# MCU.net
KiCad netlist of a schematic drawn in Altium Designer
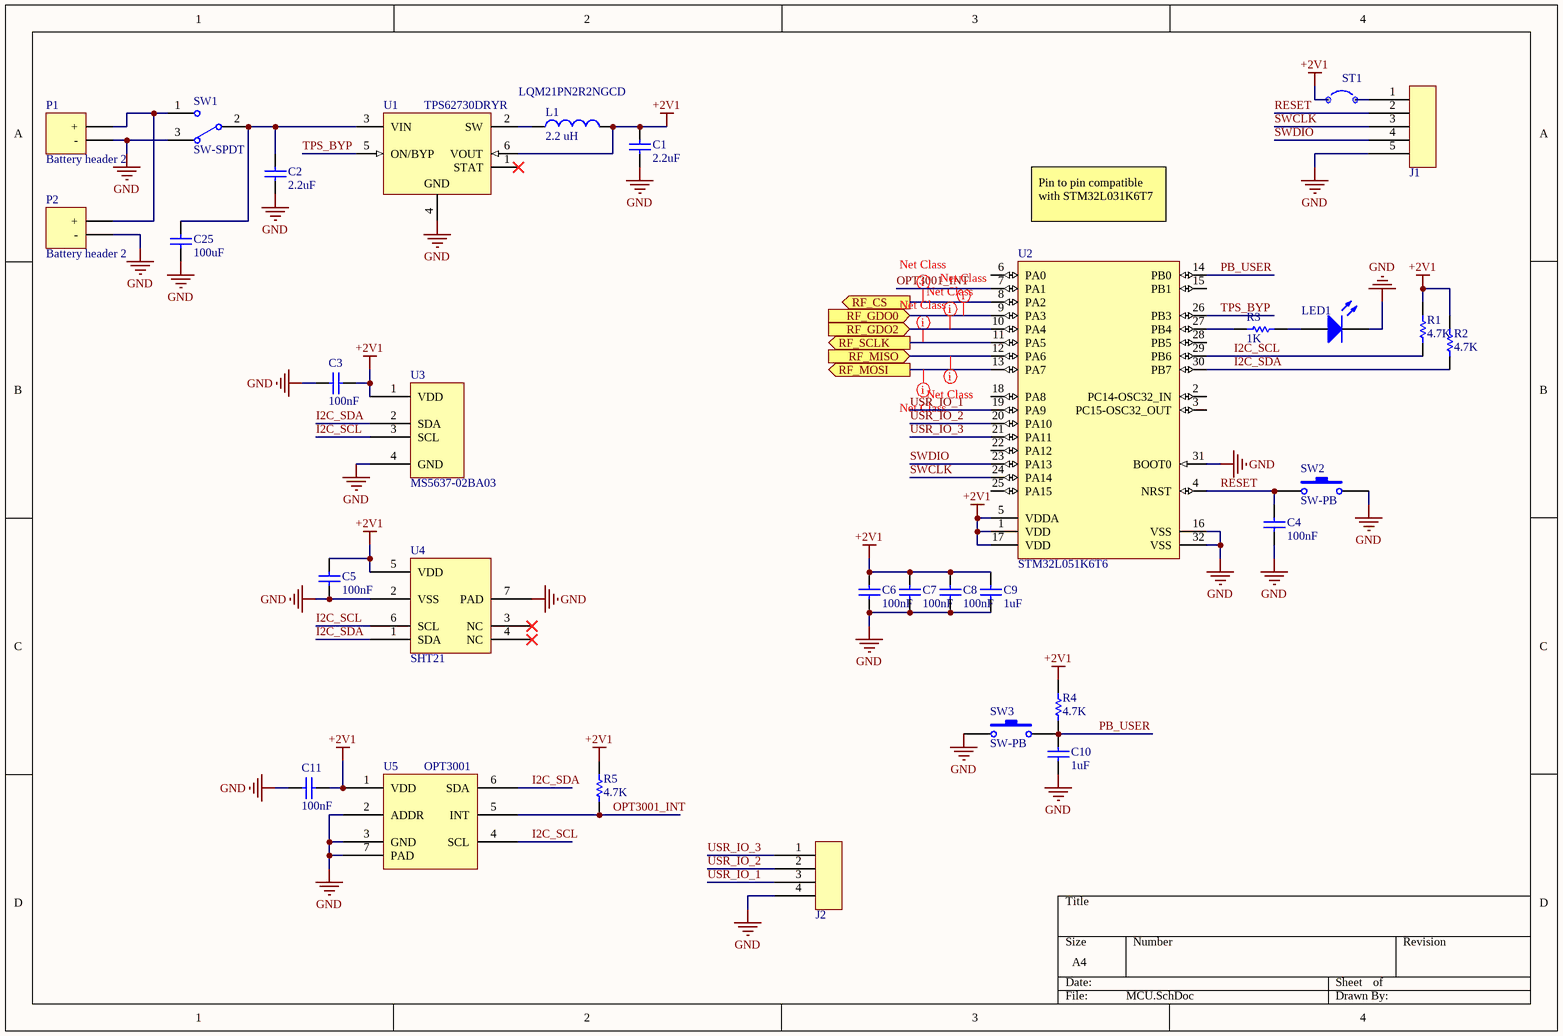
[diagram p0: MCU.SchDoc]

(export (version "E")
  (design (tool "Eeschema 10.0.6"))
  (components
    (comp (ref "C1")
      (value "2.2uF")
      (footprint "0402_ipc")
      (description "Capacitor")
      (fields
        (field (name "PARTNUMBER") "GRM155R60J225ME95D")
        (field (name "Comment") "Cap")
        (field (name "PUBLISHER") "Altium Limited")
      )
      (libsource (lib "LucasLib") (part "Cap"))
    )
    (comp (ref "C2")
      (value "2.2uF")
      (footprint "0402_ipc")
      (description "Capacitor")
      (fields
        (field (name "PARTNUMBER") "GRM155R60J225ME95D")
        (field (name "Comment") "Cap")
        (field (name "PUBLISHER") "Altium Limited")
      )
      (libsource (lib "LucasLib") (part "Cap"))
    )
    (comp (ref "C3")
      (value "100nF")
      (footprint "0402_ipc")
      (description "Capacitor")
      (fields
        (field (name "PARTNUMBER") "GRM155R71C104KA88D")
        (field (name "Comment") "Cap")
        (field (name "PUBLISHER") "Altium Limited")
      )
      (libsource (lib "LucasLib") (part "Cap"))
    )
    (comp (ref "C4")
      (value "100nF")
      (footprint "0402_ipc")
      (description "Capacitor")
      (fields
        (field (name "PARTNUMBER") "GRM155R71C104KA88D")
        (field (name "Comment") "Cap")
        (field (name "PUBLISHER") "Altium Limited")
      )
      (libsource (lib "LucasLib") (part "Cap"))
    )
    (comp (ref "C5")
      (value "100nF")
      (footprint "0402_ipc")
      (description "Capacitor")
      (fields
        (field (name "PARTNUMBER") "GRM155R71C104KA88D")
        (field (name "Comment") "Cap")
        (field (name "PUBLISHER") "Altium Limited")
      )
      (libsource (lib "LucasLib") (part "Cap"))
    )
    (comp (ref "C6")
      (value "100nF")
      (footprint "0402_ipc")
      (description "Capacitor")
      (fields
        (field (name "PARTNUMBER") "GRM155R71C104KA88D")
        (field (name "Comment") "Cap")
        (field (name "PUBLISHER") "Altium Limited")
      )
      (libsource (lib "LucasLib") (part "Cap"))
    )
    (comp (ref "C7")
      (value "100nF")
      (footprint "0402_ipc")
      (description "Capacitor")
      (fields
        (field (name "PARTNUMBER") "GRM155R71C104KA88D")
        (field (name "Comment") "Cap")
        (field (name "PUBLISHER") "Altium Limited")
      )
      (libsource (lib "LucasLib") (part "Cap"))
    )
    (comp (ref "C8")
      (value "100nF")
      (footprint "0402_ipc")
      (description "Capacitor")
      (fields
        (field (name "PARTNUMBER") "GRM155R71C104KA88D")
        (field (name "Comment") "Cap")
        (field (name "PUBLISHER") "Altium Limited")
      )
      (libsource (lib "LucasLib") (part "Cap"))
    )
    (comp (ref "C9")
      (value "1uF")
      (footprint "0402_ipc")
      (description "Capacitor")
      (fields
        (field (name "PARTNUMBER") "GRM155R61C105KA12D")
        (field (name "Comment") "Cap")
        (field (name "PUBLISHER") "Altium Limited")
      )
      (libsource (lib "LucasLib") (part "Cap"))
    )
    (comp (ref "C10")
      (value "1uF")
      (footprint "0402_ipc")
      (description "Capacitor")
      (fields
        (field (name "PARTNUMBER") "GRM155R61C105KA12D")
        (field (name "Comment") "Cap")
        (field (name "PUBLISHER") "Altium Limited")
      )
      (libsource (lib "LucasLib") (part "Cap"))
    )
    (comp (ref "C11")
      (value "100nF")
      (footprint "0402_ipc")
      (description "Capacitor")
      (fields
        (field (name "PARTNUMBER") "GRM155R71C104KA88D")
        (field (name "Comment") "Cap")
        (field (name "PUBLISHER") "Altium Limited")
      )
      (libsource (lib "LucasLib") (part "Cap"))
    )
    (comp (ref "C25")
      (value "100uF")
      (footprint "1206_IPC")
      (description "Capacitor")
      (fields
        (field (name "PARTNUMBER") "GRM31CR60J157ME11L")
        (field (name "Comment") "Cap")
        (field (name "PUBLISHER") "Altium Limited")
      )
      (libsource (lib "LucasLib") (part "Cap"))
    )
    (comp (ref "J1")
      (value "CONN_5")
      (footprint "MOLEX_5_1.27")
      (description "5 pin connector")
      (fields (field (name "PARTNUMBER") "53048-0510"))
      (libsource (lib "LucasLib") (part "CONN_5"))
    )
    (comp (ref "J2")
      (value "CONN_4")
      (footprint "HDR1X4_100mil")
      (description "4 pin connector")
      (fields (field (name "PARTNUMBER") "Pin Header"))
      (libsource (lib "LucasLib") (part "CONN_4"))
    )
    (comp (ref "L1")
      (value "2.2 uH")
      (footprint "0805_IPC")
      (description "Inductor")
      (fields (field (name "PARTNUMBER") "LQM21PN2R2NGCD"))
      (libsource (lib "LucasLib") (part "Inductor"))
    )
    (comp (ref "LED1")
      (value "LED")
      (footprint "0805_IPC")
      (fields (field (name "PARTNUMBER") "SML-H12M8TT86"))
      (libsource (lib "LucasLib") (part "LED"))
    )
    (comp (ref "P1")
      (value "Battery header 2")
      (footprint "HDR1X2_100mil")
      (fields (field (name "PARTNUMBER") "Pin Header") (field (name "PUBLISHER") "Altium Limited"))
      (libsource (lib "LucasLib") (part "Battery header 2"))
    )
    (comp (ref "P2")
      (value "Battery header 2")
      (footprint "SMTU2450N-LF")
      (fields (field (name "PARTNUMBER") "SMTU 2450N-1-LF") (field (name "PUBLISHER") "Altium Limited"))
      (libsource (lib "LucasLib") (part "Battery header 2"))
    )
    (comp (ref "R1")
      (value "4.7K")
      (footprint "0402_ipc")
      (description "Resistor")
      (fields (field (name "PARTNUMBER") "ERJ2GEJ472X") (field (name "Comment") "Res"))
      (libsource (lib "LucasLib") (part "Res"))
    )
    (comp (ref "R2")
      (value "4.7K")
      (footprint "0402_ipc")
      (description "Resistor")
      (fields (field (name "PARTNUMBER") "ERJ2GEJ472X") (field (name "Comment") "Res"))
      (libsource (lib "LucasLib") (part "Res"))
    )
    (comp (ref "R3")
      (value "1K")
      (footprint "0402_ipc")
      (description "Resistor")
      (fields (field (name "PARTNUMBER") "MC00625W040211K") (field (name "Comment") "Res"))
      (libsource (lib "LucasLib") (part "Res"))
    )
    (comp (ref "R4")
      (value "4.7K")
      (footprint "0402_ipc")
      (description "Resistor")
      (fields (field (name "PARTNUMBER") "ERJ2GEJ472X") (field (name "Comment") "Res"))
      (libsource (lib "LucasLib") (part "Res"))
    )
    (comp (ref "R5")
      (value "4.7K")
      (footprint "0402_ipc")
      (description "Resistor")
      (fields (field (name "PARTNUMBER") "ERJ2GEJ472X") (field (name "Comment") "Res"))
      (libsource (lib "LucasLib") (part "Res"))
    )
    (comp (ref "ST1") (value "STRAP") (footprint "STRAP") (libsource (lib "LucasLib") (part "STRAP")))
    (comp (ref "SW1")
      (value "SW-SPDT")
      (footprint "PCM12SMTR")
      (description "SPDT Switch")
      (fields (field (name "PARTNUMBER") "PCM12SMTR"))
      (libsource (lib "LucasLib") (part "SW-SPDT"))
    )
    (comp (ref "SW2")
      (value "SW-PB")
      (footprint "B3U-1000P")
      (description "Tactile Switch")
      (fields (field (name "PARTNUMBER") "B3U-1000P"))
      (libsource (lib "LucasLib") (part "SW-PB"))
    )
    (comp (ref "SW3")
      (value "SW-PB")
      (footprint "MCDTS-2")
      (description "Tactile Switch")
      (fields (field (name "PARTNUMBER") "MCDTS2-4N"))
      (libsource (lib "LucasLib") (part "SW-PB"))
    )
    (comp (ref "U1")
      (value "TPS62730DRYR")
      (footprint "DRY6")
      (fields (field (name "MANUFACTURER") "Texas Instruments") (field (name "PARTNUMBER") "TPS62730DRYT"))
      (libsource (lib "TI Power Management Step-Down Regulator") (part "TPS62730DRYR"))
    )
    (comp (ref "U2")
      (value "STM32L051K6T6")
      (footprint "STM-LQFP32_L")
      (fields (field (name "PARTNUMBER") "STM32L031K6T7") (field (name "MANUFACTURER") "STMicroelectronics"))
      (libsource (lib "Altium Content Vault") (part "CMP-1341-00001-1"))
    )
    (comp (ref "U3")
      (value "MS5637-02BA03")
      (footprint "MS5637-02BA03")
      (description "Low Voltage Barometric Pressure Sensor")
      (fields (field (name "PARTNUMBER") "MS563702BA03-50"))
      (libsource (lib "LucasLib") (part "MS5637-02BA03"))
    )
    (comp (ref "U4")
      (value "SHT21")
      (footprint "SHT21")
      (description "Humidity and Temperature Sensor")
      (libsource (lib "LucasLib") (part "SHT21"))
    )
    (comp (ref "U5")
      (value "OPT3001")
      (footprint "OPT3001")
      (description "Light sensor")
      (fields (field (name "PARTNUMBER") "OPT3001DNPT"))
      (libsource (lib "LucasLib") (part "OPT3001"))
    )
  )
  (nets
    (net (code "1") (name "+2V1") (class "Default")
      (node (ref "C1") (pin "2") (pinfunction "2_2") (pintype "passive"))
      (node (ref "C11") (pin "2") (pinfunction "2_2") (pintype "passive"))
      (node (ref "C3") (pin "1") (pinfunction "1_1") (pintype "passive"))
      (node (ref "C5") (pin "1") (pinfunction "1_1") (pintype "passive"))
      (node (ref "C6") (pin "2") (pinfunction "2_2") (pintype "passive"))
      (node (ref "C7") (pin "2") (pinfunction "2_2") (pintype "passive"))
      (node (ref "C8") (pin "2") (pinfunction "2_2") (pintype "passive"))
      (node (ref "C9") (pin "2") (pinfunction "2_2") (pintype "passive"))
      (node (ref "L1") (pin "2") (pinfunction "2_2") (pintype "passive"))
      (node (ref "R1") (pin "2") (pinfunction "2_2") (pintype "passive"))
      (node (ref "R2") (pin "2") (pinfunction "2_2") (pintype "passive"))
      (node (ref "R4") (pin "2") (pinfunction "2_2") (pintype "passive"))
      (node (ref "R5") (pin "2") (pinfunction "2_2") (pintype "passive"))
      (node (ref "ST1") (pin "1") (pintype "passive"))
      (node (ref "U1") (pin "6") (pinfunction "VOUT_6") (pintype "input"))
      (node (ref "U2") (pin "1") (pinfunction "VDD_1") (pintype "power_in"))
      (node (ref "U2") (pin "17") (pinfunction "VDD_17") (pintype "power_in"))
      (node (ref "U2") (pin "5") (pinfunction "VDDA_5") (pintype "power_in"))
      (node (ref "U3") (pin "1") (pinfunction "VDD_1") (pintype "passive"))
      (node (ref "U4") (pin "5") (pinfunction "VDD_5") (pintype "passive"))
      (node (ref "U5") (pin "1") (pinfunction "VDD_1") (pintype "passive"))
    )
    (net (code "2") (name "/I2C_SCL") (class "Default")
      (node (ref "R1") (pin "1") (pinfunction "1_1") (pintype "passive"))
      (node (ref "U2") (pin "29") (pinfunction "PB6_29") (pintype "bidirectional"))
      (node (ref "U3") (pin "3") (pinfunction "SCL_3") (pintype "passive"))
      (node (ref "U4") (pin "6") (pinfunction "SCL_6") (pintype "passive"))
      (node (ref "U5") (pin "4") (pinfunction "SCL_4") (pintype "passive"))
    )
    (net (code "3") (name "/I2C_SDA") (class "Default")
      (node (ref "R2") (pin "1") (pinfunction "1_1") (pintype "passive"))
      (node (ref "U2") (pin "30") (pinfunction "PB7_30") (pintype "bidirectional"))
      (node (ref "U3") (pin "2") (pinfunction "SDA_2") (pintype "passive"))
      (node (ref "U4") (pin "1") (pinfunction "SDA_1") (pintype "passive"))
      (node (ref "U5") (pin "6") (pinfunction "SDA_6") (pintype "passive"))
    )
    (net (code "4") (name "/OPT3001_INT") (class "Default")
      (node (ref "R5") (pin "1") (pinfunction "1_1") (pintype "passive"))
      (node (ref "U2") (pin "7") (pinfunction "PA1_7") (pintype "bidirectional"))
      (node (ref "U5") (pin "5") (pinfunction "INT_5") (pintype "passive"))
    )
    (net (code "5") (name "/PB_USER") (class "Default")
      (node (ref "C10") (pin "2") (pinfunction "2_2") (pintype "passive"))
      (node (ref "R4") (pin "1") (pinfunction "1_1") (pintype "passive"))
      (node (ref "SW3") (pin "2") (pinfunction "2_2") (pintype "passive"))
      (node (ref "U2") (pin "14") (pinfunction "PB0_14") (pintype "bidirectional"))
    )
    (net (code "6") (name "/RESET") (class "Default")
      (node (ref "C4") (pin "2") (pinfunction "2_2") (pintype "passive"))
      (node (ref "J1") (pin "2") (pinfunction "2_2") (pintype "passive"))
      (node (ref "SW2") (pin "1") (pinfunction "1_1") (pintype "passive"))
      (node (ref "U2") (pin "4") (pinfunction "NRST_4") (pintype "bidirectional"))
    )
    (net (code "7") (name "/RF_CS") (class "Default")
      (node (ref "U2") (pin "8") (pinfunction "PA2_8") (pintype "bidirectional"))
    )
    (net (code "8") (name "/RF_GDO0") (class "Default")
      (node (ref "U2") (pin "9") (pinfunction "PA3_9") (pintype "bidirectional"))
    )
    (net (code "9") (name "/RF_GDO2") (class "Default")
      (node (ref "U2") (pin "10") (pinfunction "PA4_10") (pintype "bidirectional"))
    )
    (net (code "10") (name "/RF_MISO") (class "Default")
      (node (ref "U2") (pin "12") (pinfunction "PA6_12") (pintype "bidirectional"))
    )
    (net (code "11") (name "/RF_MOSI") (class "Default")
      (node (ref "U2") (pin "13") (pinfunction "PA7_13") (pintype "bidirectional"))
    )
    (net (code "12") (name "/RF_SCLK") (class "Default")
      (node (ref "U2") (pin "11") (pinfunction "PA5_11") (pintype "bidirectional"))
    )
    (net (code "13") (name "/SWCLK") (class "Default")
      (node (ref "J1") (pin "3") (pinfunction "3_3") (pintype "passive"))
      (node (ref "U2") (pin "24") (pinfunction "PA14_24") (pintype "bidirectional"))
    )
    (net (code "14") (name "/SWDIO") (class "Default")
      (node (ref "J1") (pin "4") (pinfunction "4_4") (pintype "passive"))
      (node (ref "U2") (pin "23") (pinfunction "PA13_23") (pintype "bidirectional"))
    )
    (net (code "15") (name "/TPS_BYP") (class "Default")
      (node (ref "U1") (pin "5") (pinfunction "ON/BYP_5") (pintype "input"))
      (node (ref "U2") (pin "26") (pinfunction "PB3_26") (pintype "bidirectional"))
    )
    (net (code "16") (name "/USR_IO_1") (class "Default")
      (node (ref "J2") (pin "3") (pinfunction "3_3") (pintype "passive"))
      (node (ref "U2") (pin "19") (pinfunction "PA9_19") (pintype "bidirectional"))
    )
    (net (code "17") (name "/USR_IO_2") (class "Default")
      (node (ref "J2") (pin "2") (pinfunction "2_2") (pintype "passive"))
      (node (ref "U2") (pin "20") (pinfunction "PA10_20") (pintype "bidirectional"))
    )
    (net (code "18") (name "/USR_IO_3") (class "Default")
      (node (ref "J2") (pin "1") (pinfunction "1_1") (pintype "passive"))
      (node (ref "U2") (pin "21") (pinfunction "PA11_21") (pintype "bidirectional"))
    )
    (net (code "19") (name "GND") (class "Default")
      (node (ref "C1") (pin "1") (pinfunction "1_1") (pintype "passive"))
      (node (ref "C10") (pin "1") (pinfunction "1_1") (pintype "passive"))
      (node (ref "C11") (pin "1") (pinfunction "1_1") (pintype "passive"))
      (node (ref "C2") (pin "1") (pinfunction "1_1") (pintype "passive"))
      (node (ref "C25") (pin "1") (pinfunction "1_1") (pintype "passive"))
      (node (ref "C3") (pin "2") (pinfunction "2_2") (pintype "passive"))
      (node (ref "C4") (pin "1") (pinfunction "1_1") (pintype "passive"))
      (node (ref "C5") (pin "2") (pinfunction "2_2") (pintype "passive"))
      (node (ref "C6") (pin "1") (pinfunction "1_1") (pintype "passive"))
      (node (ref "C7") (pin "1") (pinfunction "1_1") (pintype "passive"))
      (node (ref "C8") (pin "1") (pinfunction "1_1") (pintype "passive"))
      (node (ref "C9") (pin "1") (pinfunction "1_1") (pintype "passive"))
      (node (ref "J1") (pin "5") (pinfunction "5_5") (pintype "passive"))
      (node (ref "J2") (pin "4") (pinfunction "4_4") (pintype "passive"))
      (node (ref "LED1") (pin "2") (pinfunction "K_2") (pintype "passive"))
      (node (ref "P1") (pin "2") (pinfunction "-_2") (pintype "passive"))
      (node (ref "P2") (pin "2") (pinfunction "-_2") (pintype "passive"))
      (node (ref "SW1") (pin "3") (pinfunction "3_3") (pintype "passive"))
      (node (ref "SW2") (pin "2") (pinfunction "2_2") (pintype "passive"))
      (node (ref "SW3") (pin "1") (pinfunction "1_1") (pintype "passive"))
      (node (ref "U1") (pin "4") (pinfunction "GND_4") (pintype "power_in"))
      (node (ref "U2") (pin "16") (pinfunction "VSS_16") (pintype "power_in"))
      (node (ref "U2") (pin "31") (pinfunction "BOOT0_31") (pintype "input"))
      (node (ref "U2") (pin "32") (pinfunction "VSS_32") (pintype "power_in"))
      (node (ref "U3") (pin "4") (pinfunction "GND_4") (pintype "passive"))
      (node (ref "U4") (pin "2") (pinfunction "VSS_2") (pintype "passive"))
      (node (ref "U4") (pin "7") (pinfunction "PAD_7") (pintype "passive"))
      (node (ref "U5") (pin "2") (pinfunction "ADDR_2") (pintype "passive"))
      (node (ref "U5") (pin "3") (pinfunction "GND_3") (pintype "passive"))
      (node (ref "U5") (pin "7") (pinfunction "PAD_7") (pintype "passive"))
    )
    (net (code "20") (name "Net-(J1-Pad1)") (class "Default")
      (node (ref "J1") (pin "1") (pinfunction "1_1") (pintype "passive"))
      (node (ref "ST1") (pin "2") (pintype "passive"))
    )
    (net (code "21") (name "Net-(LED1-A)") (class "Default")
      (node (ref "LED1") (pin "1") (pinfunction "A_1") (pintype "passive"))
      (node (ref "R3") (pin "2") (pinfunction "2_2") (pintype "passive"))
    )
    (net (code "22") (name "Net-(P1-+)") (class "Default")
      (node (ref "P1") (pin "1") (pinfunction "+_1") (pintype "passive"))
      (node (ref "P2") (pin "1") (pinfunction "+_1") (pintype "passive"))
      (node (ref "SW1") (pin "1") (pinfunction "1_1") (pintype "passive"))
    )
    (net (code "23") (name "Net-(U1-SW)") (class "Default")
      (node (ref "L1") (pin "1") (pinfunction "1_1") (pintype "passive"))
      (node (ref "U1") (pin "2") (pinfunction "SW_2") (pintype "power_in"))
    )
    (net (code "24") (name "Net-(U1-VIN)") (class "Default")
      (node (ref "C2") (pin "2") (pinfunction "2_2") (pintype "passive"))
      (node (ref "C25") (pin "2") (pinfunction "2_2") (pintype "passive"))
      (node (ref "SW1") (pin "2") (pinfunction "2_2") (pintype "passive"))
      (node (ref "U1") (pin "3") (pinfunction "VIN_3") (pintype "power_in"))
    )
    (net (code "25") (name "Net-(U2-PB4)") (class "Default")
      (node (ref "R3") (pin "1") (pinfunction "1_1") (pintype "passive"))
      (node (ref "U2") (pin "27") (pinfunction "PB4_27") (pintype "bidirectional"))
    )
    (net (code "26") (name "unconnected-(U1-STAT-Pad1)") (class "Default")
      (node (ref "U1") (pin "1") (pinfunction "STAT_1") (pintype "tri_state+no_connect"))
    )
    (net (code "27") (name "unconnected-(U2-PA0-Pad6)") (class "Default")
      (node (ref "U2") (pin "6") (pinfunction "PA0_6") (pintype "bidirectional"))
    )
    (net (code "28") (name "unconnected-(U2-PA8-Pad18)") (class "Default")
      (node (ref "U2") (pin "18") (pinfunction "PA8_18") (pintype "bidirectional"))
    )
    (net (code "29") (name "unconnected-(U2-PA12-Pad22)") (class "Default")
      (node (ref "U2") (pin "22") (pinfunction "PA12_22") (pintype "bidirectional"))
    )
    (net (code "30") (name "unconnected-(U2-PA15-Pad25)") (class "Default")
      (node (ref "U2") (pin "25") (pinfunction "PA15_25") (pintype "bidirectional"))
    )
    (net (code "31") (name "unconnected-(U2-PB1-Pad15)") (class "Default")
      (node (ref "U2") (pin "15") (pinfunction "PB1_15") (pintype "bidirectional"))
    )
    (net (code "32") (name "unconnected-(U2-PB5-Pad28)") (class "Default")
      (node (ref "U2") (pin "28") (pinfunction "PB5_28") (pintype "bidirectional"))
    )
    (net (code "33") (name "unconnected-(U2-PC14-OSC32_IN-Pad2)") (class "Default")
      (node (ref "U2") (pin "2") (pinfunction "PC14-OSC32_IN_2") (pintype "bidirectional"))
    )
    (net (code "34") (name "unconnected-(U2-PC15-OSC32_OUT-Pad3)") (class "Default")
      (node (ref "U2") (pin "3") (pinfunction "PC15-OSC32_OUT_3") (pintype "bidirectional"))
    )
    (net (code "35") (name "unconnected-(U4-NC-Pad3)") (class "Default")
      (node (ref "U4") (pin "3") (pinfunction "NC_3") (pintype "passive+no_connect"))
    )
    (net (code "36") (name "unconnected-(U4-NC-Pad4)") (class "Default")
      (node (ref "U4") (pin "4") (pinfunction "NC_4") (pintype "passive+no_connect"))
    )
  )
)
